# npsu.net
KiCad netlist of a schematic drawn in EAGLE
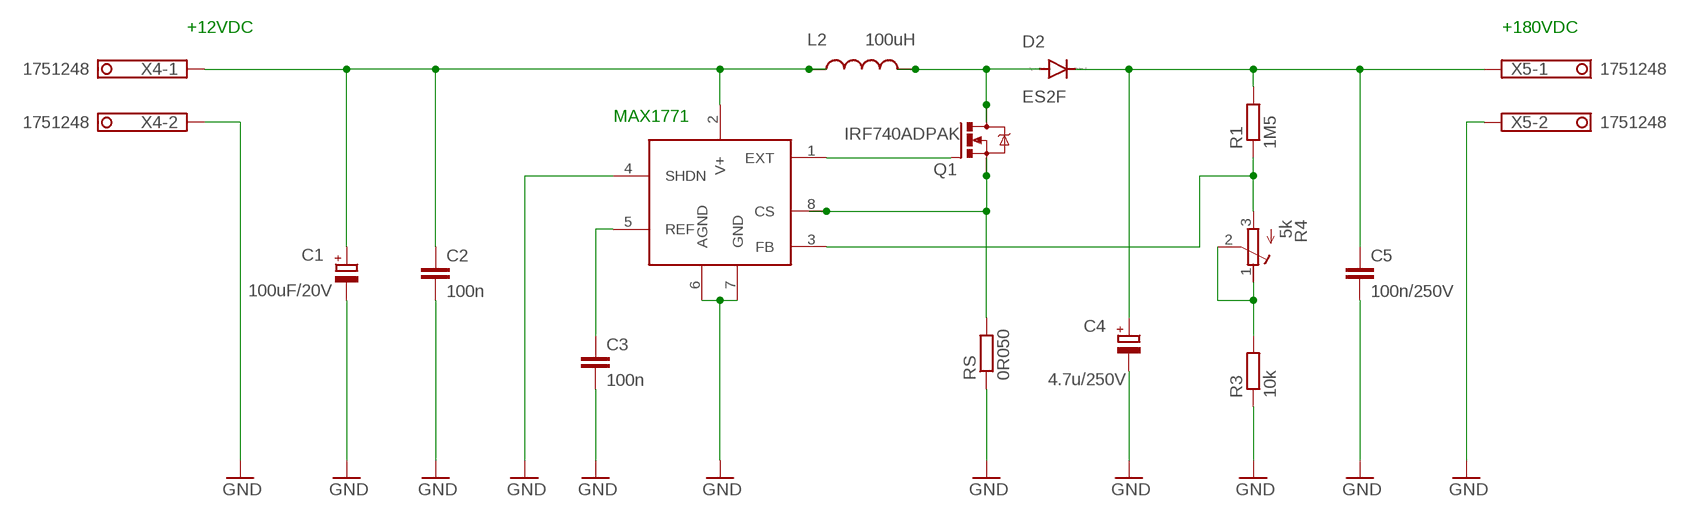
[diagram p0: schematic, sheet 1]

(export (version "E")
  (design (tool "Eeschema 10.0.6"))
  (components
    (comp (ref "C1")
      (value "100uF/20V")
      (footprint "eagle-import:SMC_D")
      (libsource (lib "eagle-import") (part "rcl_334_CPOL-EUSMCD"))
    )
    (comp (ref "C2")
      (value "100n")
      (footprint "eagle-import:C0805")
      (libsource (lib "eagle-import") (part "C-EUC0805"))
    )
    (comp (ref "C3")
      (value "100n")
      (footprint "eagle-import:C0805")
      (libsource (lib "eagle-import") (part "C-EUC0805"))
    )
    (comp (ref "C4")
      (value "4.7u/250V")
      (footprint "eagle-import:140CLH-0810")
      (libsource (lib "eagle-import") (part "CPOL-EU140CLH-0810"))
    )
    (comp (ref "C5")
      (value "100n/250V")
      (footprint "eagle-import:C1210")
      (libsource (lib "eagle-import") (part "C-EUC1210"))
    )
    (comp (ref "D2")
      (value "ES2F")
      (footprint "eagle-import:SMB")
      (libsource (lib "eagle-import") (part "ES2D"))
    )
    (comp (ref "L2")
      (value "100uH")
      (footprint "eagle-import:DR1030")
      (libsource (lib "eagle-import") (part "INDUCTORDR1030"))
    )
    (comp (ref "MAX1771")
      (value "MAX1771")
      (footprint "eagle-import:SO08")
      (libsource (lib "eagle-import") (part "MAX1771"))
    )
    (comp (ref "Q1")
      (value "IRF740ADPAK")
      (footprint "eagle-import:TO-263_D2PAK")
      (libsource (lib "eagle-import") (part "IRF740ADPAK"))
    )
    (comp (ref "R1")
      (value "1M5")
      (footprint "eagle-import:R0805")
      (libsource (lib "eagle-import") (part "R-EU_R0805"))
    )
    (comp (ref "R3")
      (value "10k")
      (footprint "eagle-import:R0805")
      (libsource (lib "eagle-import") (part "R-EU_R0805"))
    )
    (comp (ref "R4")
      (value "5k")
      (footprint "eagle-import:RTRIM3314G")
      (libsource (lib "eagle-import") (part "R-TRIMM3314G"))
    )
    (comp (ref "RS")
      (value "0R050")
      (footprint "eagle-import:R1206")
      (libsource (lib "eagle-import") (part "R-EU_R1206"))
    )
    (comp (ref "X4")
      (value "1751248")
      (footprint "eagle-import:1751248")
      (libsource (lib "eagle-import") (part "1751248"))
    )
    (comp (ref "X5")
      (value "1751248")
      (footprint "eagle-import:1751248")
      (libsource (lib "eagle-import") (part "1751248"))
    )
  )
  (nets
    (net (code "1") (name "GND") (class "Default")
      (node (ref "C1") (pin "-") (pinfunction "-_-") (pintype "passive"))
      (node (ref "C2") (pin "2") (pinfunction "2_2") (pintype "passive"))
      (node (ref "C3") (pin "2") (pinfunction "2_2") (pintype "passive"))
      (node (ref "C4") (pin "-") (pinfunction "-_-") (pintype "passive"))
      (node (ref "C5") (pin "2") (pinfunction "2_2") (pintype "passive"))
      (node (ref "MAX1771") (pin "4") (pinfunction "SHDN_4") (pintype "bidirectional"))
      (node (ref "MAX1771") (pin "6") (pinfunction "AGND_6") (pintype "bidirectional"))
      (node (ref "MAX1771") (pin "7") (pinfunction "GND_7") (pintype "bidirectional"))
      (node (ref "R3") (pin "1") (pinfunction "1_1") (pintype "passive"))
      (node (ref "RS") (pin "1") (pinfunction "1_1") (pintype "passive"))
      (node (ref "X4") (pin "2") (pinfunction "K_2") (pintype "passive"))
      (node (ref "X5") (pin "2") (pinfunction "K_2") (pintype "passive"))
    )
    (net (code "2") (name "Net-(MAX1771-CS)") (class "Default")
      (node (ref "MAX1771") (pin "8") (pinfunction "CS_8") (pintype "bidirectional"))
      (node (ref "Q1") (pin "3") (pinfunction "S_3") (pintype "passive"))
      (node (ref "RS") (pin "2") (pinfunction "2_2") (pintype "passive"))
    )
    (net (code "3") (name "Net-(MAX1771-EXT)") (class "Default")
      (node (ref "MAX1771") (pin "1") (pinfunction "EXT_1") (pintype "bidirectional"))
      (node (ref "Q1") (pin "1") (pinfunction "G_1") (pintype "passive"))
    )
    (net (code "4") (name "Net-(MAX1771-FB)") (class "Default")
      (node (ref "MAX1771") (pin "3") (pinfunction "FB_3") (pintype "bidirectional"))
      (node (ref "R1") (pin "1") (pinfunction "1_1") (pintype "passive"))
      (node (ref "R4") (pin "3") (pinfunction "A_3") (pintype "passive"))
    )
    (net (code "5") (name "Net-(MAX1771-REF)") (class "Default")
      (node (ref "C3") (pin "1") (pinfunction "1_1") (pintype "passive"))
      (node (ref "MAX1771") (pin "5") (pinfunction "REF_5") (pintype "bidirectional"))
    )
    (net (code "6") (name "Net-(MAX1771-V+)") (class "Default")
      (node (ref "C1") (pin "+") (pinfunction "+_+") (pintype "passive"))
      (node (ref "C2") (pin "1") (pinfunction "1_1") (pintype "passive"))
      (node (ref "L2") (pin "1") (pinfunction "1_1") (pintype "passive"))
      (node (ref "MAX1771") (pin "2") (pinfunction "V+_2") (pintype "bidirectional"))
      (node (ref "X4") (pin "1") (pinfunction "K_1") (pintype "passive"))
    )
    (net (code "7") (name "Net-(Q1-D)") (class "Default")
      (node (ref "D2") (pin "A") (pinfunction "A_A") (pintype "passive"))
      (node (ref "L2") (pin "2") (pinfunction "2_2") (pintype "passive"))
      (node (ref "Q1") (pin "2") (pinfunction "D_2") (pintype "passive"))
    )
    (net (code "8") (name "Net-(R4-E)") (class "Default")
      (node (ref "R3") (pin "2") (pinfunction "2_2") (pintype "passive"))
      (node (ref "R4") (pin "1") (pinfunction "E_1") (pintype "passive"))
      (node (ref "R4") (pin "2") (pinfunction "S_2") (pintype "passive"))
    )
    (net (code "9") (name "Net-(X5A-K)") (class "Default")
      (node (ref "C4") (pin "+") (pinfunction "+_+") (pintype "passive"))
      (node (ref "C5") (pin "1") (pinfunction "1_1") (pintype "passive"))
      (node (ref "D2") (pin "C") (pinfunction "C_C") (pintype "passive"))
      (node (ref "R1") (pin "2") (pinfunction "2_2") (pintype "passive"))
      (node (ref "X5") (pin "1") (pinfunction "K_1") (pintype "passive"))
    )
  )
)
